# RoverWing-V1_0.net
KiCad netlist of a schematic drawn in EAGLE
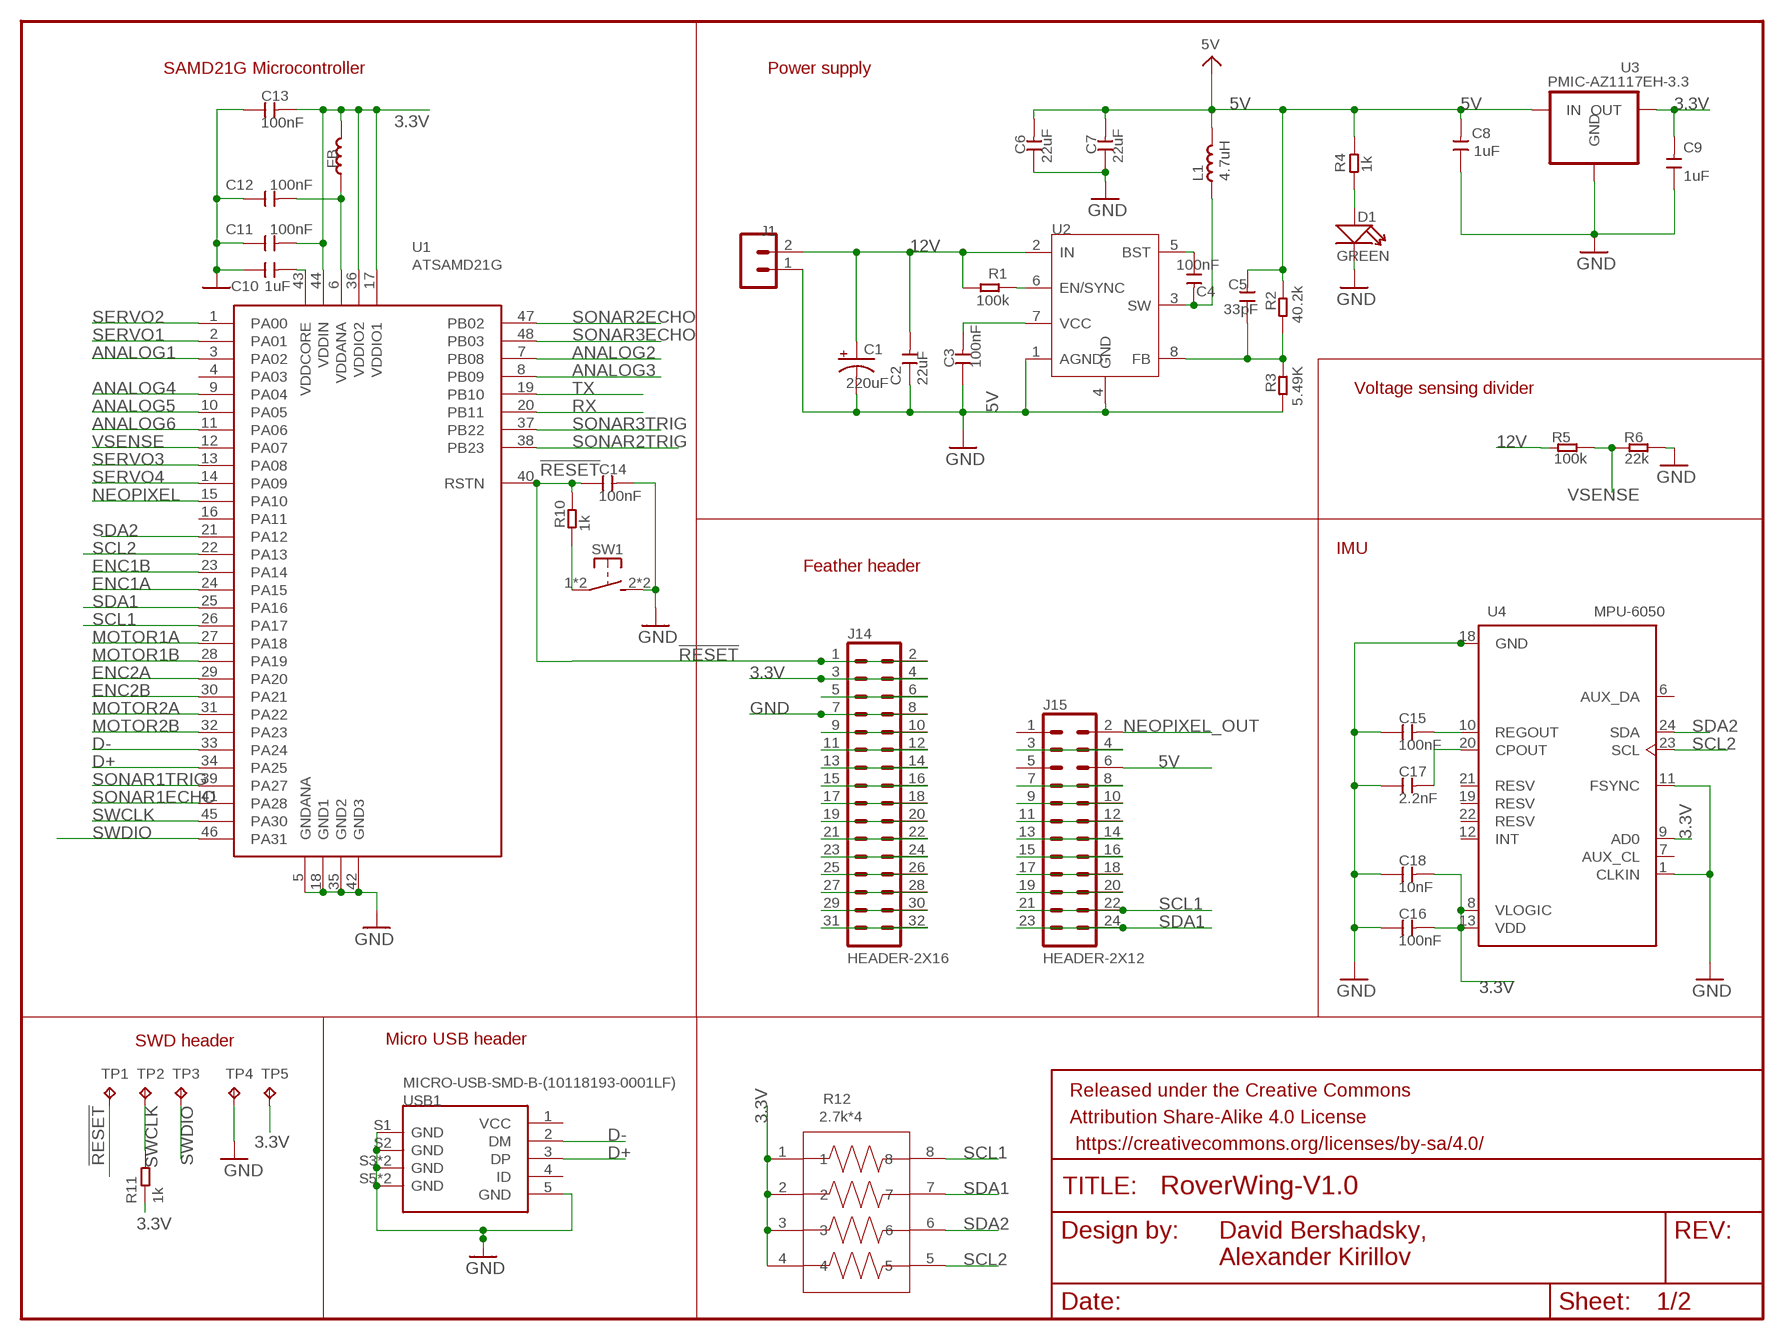
[diagram p0: schematic, sheet 1]
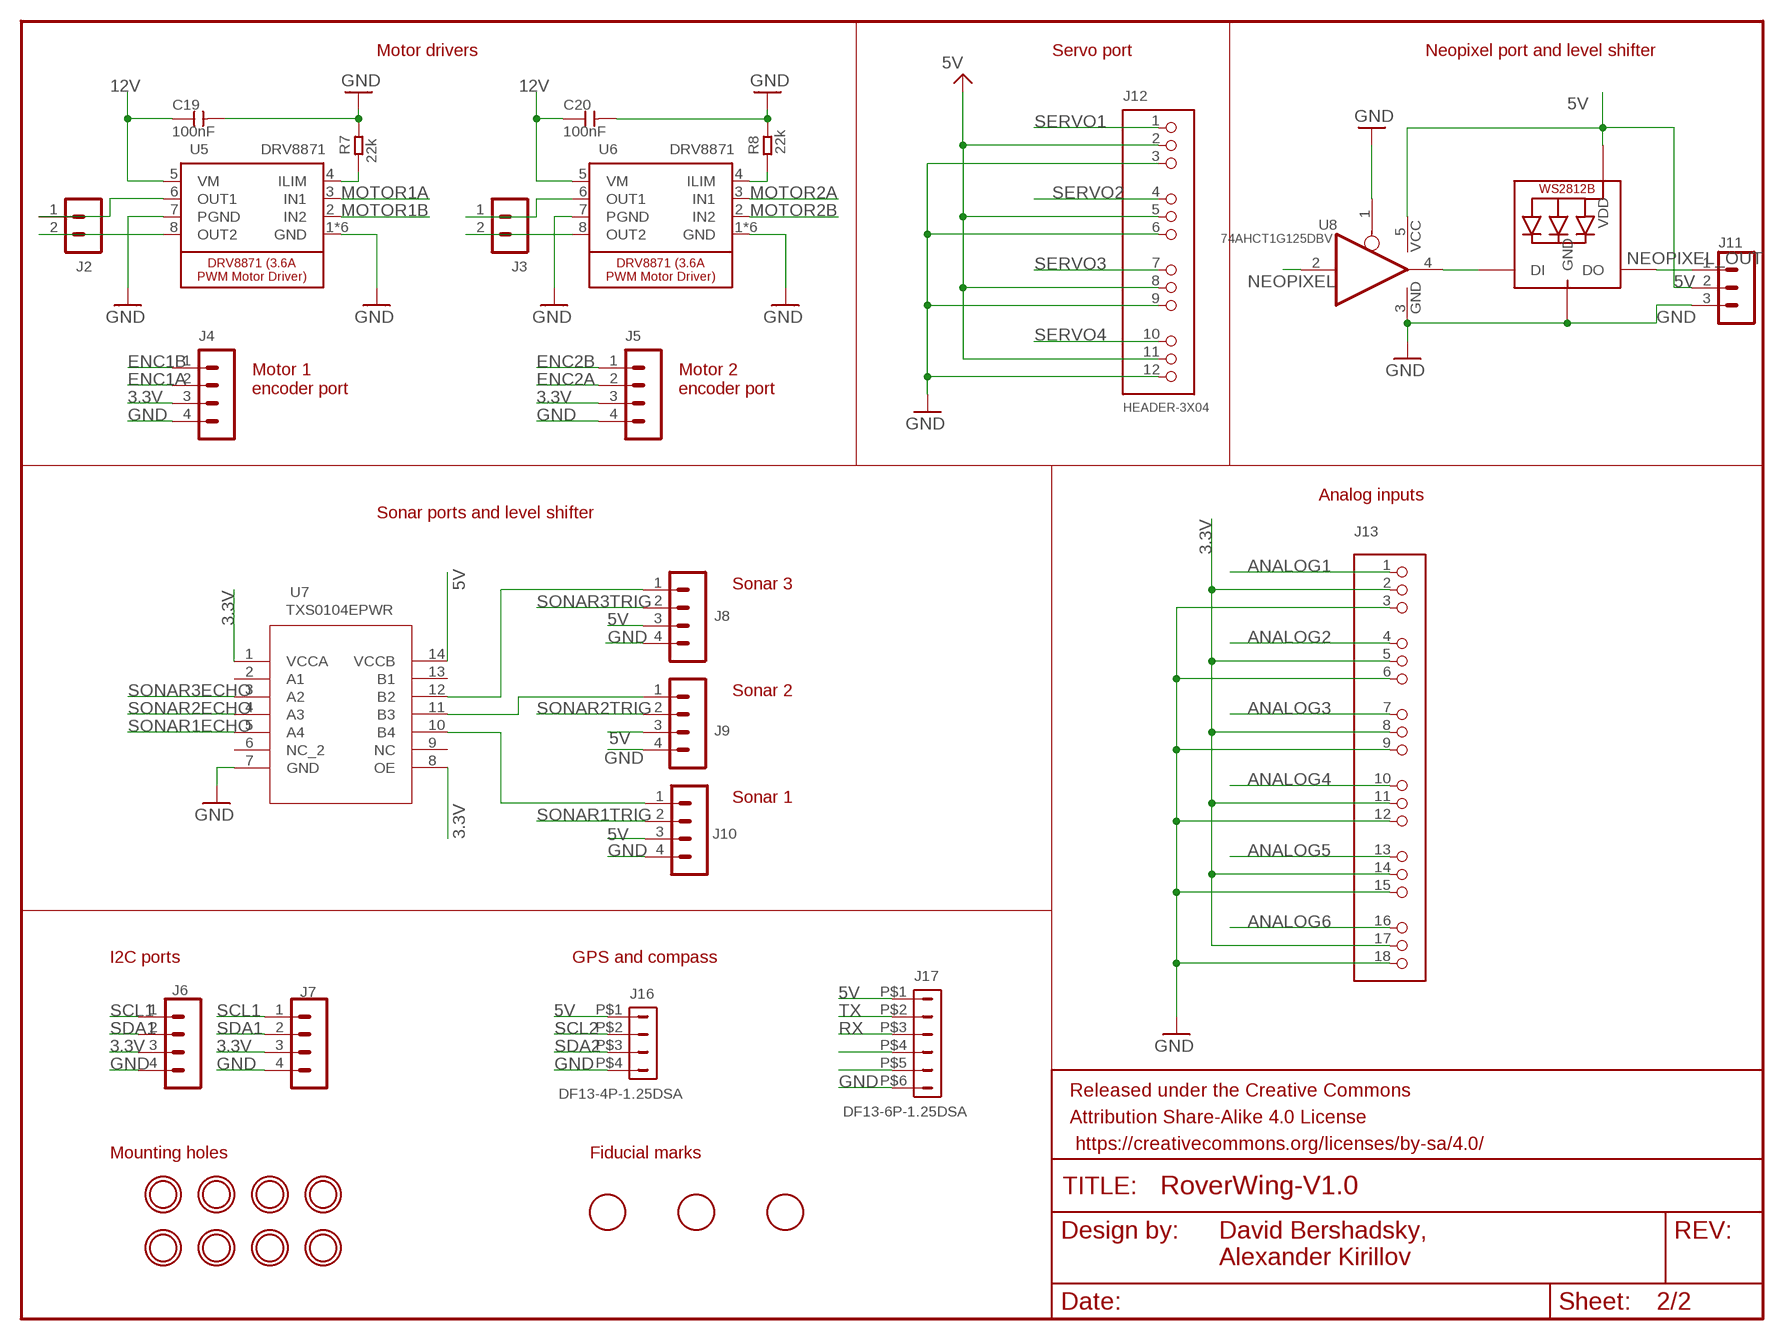
[diagram p1: schematic, sheet 2]

(export (version "E")
  (design (tool "Eeschema 10.0.6"))
  (components
    (comp (ref "C1")
      (value "220uF")
      (footprint "eagle-import:CAP-8X10.5")
      (libsource (lib "eagle-import") (part "CAP-POL-SMD-8X10.5"))
    )
    (comp (ref "C2")
      (value "22uF")
      (footprint "eagle-import:0805")
      (libsource (lib "eagle-import") (part "CAP-CERAMIC-SMD0805"))
    )
    (comp (ref "C3")
      (value "100nF")
      (footprint "eagle-import:0805")
      (libsource (lib "eagle-import") (part "CAP-CERAMIC-SMD0805"))
    )
    (comp (ref "C4")
      (value "100nF")
      (footprint "eagle-import:0805")
      (libsource (lib "eagle-import") (part "CAP-CERAMIC-SMD0805"))
    )
    (comp (ref "C5")
      (value "33pF")
      (footprint "eagle-import:0805")
      (libsource (lib "eagle-import") (part "CAP-CERAMIC-SMD0805"))
    )
    (comp (ref "C6")
      (value "22uF")
      (footprint "eagle-import:0805")
      (libsource (lib "eagle-import") (part "CAP-CERAMIC-SMD0805"))
    )
    (comp (ref "C7")
      (value "22uF")
      (footprint "eagle-import:0805")
      (libsource (lib "eagle-import") (part "CAP-CERAMIC-SMD0805"))
    )
    (comp (ref "C8")
      (value "1uF")
      (footprint "eagle-import:0805")
      (libsource (lib "eagle-import") (part "CAP-CERAMIC-SMD0805"))
    )
    (comp (ref "C9")
      (value "1uF")
      (footprint "eagle-import:0805")
      (libsource (lib "eagle-import") (part "CAP-CERAMIC-SMD0805"))
    )
    (comp (ref "C10")
      (value "1uF")
      (footprint "eagle-import:0805")
      (libsource (lib "eagle-import") (part "CAP-CERAMIC-SMD0805"))
    )
    (comp (ref "C11")
      (value "100nF")
      (footprint "eagle-import:0805")
      (libsource (lib "eagle-import") (part "CAP-CERAMIC-SMD0805"))
    )
    (comp (ref "C12")
      (value "100nF")
      (footprint "eagle-import:0805")
      (libsource (lib "eagle-import") (part "CAP-CERAMIC-SMD0805"))
    )
    (comp (ref "C13")
      (value "100nF")
      (footprint "eagle-import:0805")
      (libsource (lib "eagle-import") (part "CAP-CERAMIC-SMD0805"))
    )
    (comp (ref "C14")
      (value "100nF")
      (footprint "eagle-import:0805")
      (libsource (lib "eagle-import") (part "CAP-CERAMIC-SMD0805"))
    )
    (comp (ref "C15")
      (value "100nF")
      (footprint "eagle-import:0805")
      (libsource (lib "eagle-import") (part "CAP-CERAMIC-SMD0805"))
    )
    (comp (ref "C16")
      (value "100nF")
      (footprint "eagle-import:0805")
      (libsource (lib "eagle-import") (part "CAP-CERAMIC-SMD0805"))
    )
    (comp (ref "C17")
      (value "2.2nF")
      (footprint "eagle-import:0805")
      (libsource (lib "eagle-import") (part "CAP-CERAMIC-SMD0805"))
    )
    (comp (ref "C18")
      (value "10nF")
      (footprint "eagle-import:0805")
      (libsource (lib "eagle-import") (part "CAP-CERAMIC-SMD0805"))
    )
    (comp (ref "D1")
      (value "GREEN")
      (footprint "eagle-import:LED-0805")
      (libsource (lib "eagle-import") (part "SMD-LED-0805"))
    )
    (comp (ref "FB")
      (value "330R-1500MA")
      (footprint "eagle-import:0805")
      (fields (field (name "PARTNO") "BLM21PG331SN1D"))
      (libsource (lib "eagle-import") (part "SMD-FERRITE-BEAD-330R-1500MA(0805)"))
    )
    (comp (ref "FRAME2")
      (value "FRAME-LETTERNO_PACKAGE")
      (footprint "eagle-import:DUMMY")
      (libsource (lib "eagle-import") (part "FRAME-LETTERNO_PACKAGE"))
    )
    (comp (ref "J1")
      (value "HEADER-VH")
      (footprint "eagle-import:B2P-VH")
      (fields (field (name "PARTNO") "B2P-VH(LF)(SN)  "))
      (libsource (lib "eagle-import") (part "HEADER-VH"))
    )
    (comp (ref "J14")
      (value "HEADER-2X16")
      (footprint "eagle-import:2X16")
      (libsource (lib "eagle-import") (part "HEADER-2X16"))
    )
    (comp (ref "J15")
      (value "HEADER-2X12")
      (footprint "eagle-import:2X12")
      (libsource (lib "eagle-import") (part "HEADER-2X12"))
    )
    (comp (ref "L1")
      (value "4.7uH")
      (footprint "eagle-import:IND_TDK_7.1X6.5")
      (fields (field (name "MANUFACTURER") "TDK") (field (name "PARTNO") "SPM6530T-4R7M "))
      (libsource (lib "eagle-import") (part "IND-TDK-SPM6530T"))
    )
    (comp (ref "R1")
      (value "100k")
      (footprint "eagle-import:0805")
      (libsource (lib "eagle-import") (part "RES-SMD-0805"))
    )
    (comp (ref "R2")
      (value "40.2k")
      (footprint "eagle-import:0805")
      (libsource (lib "eagle-import") (part "RES-SMD-0805"))
    )
    (comp (ref "R3")
      (value "5.49K")
      (footprint "eagle-import:0805")
      (libsource (lib "eagle-import") (part "RES-SMD-0805"))
    )
    (comp (ref "R4")
      (value "1k")
      (footprint "eagle-import:0805")
      (libsource (lib "eagle-import") (part "RES-SMD-0805"))
    )
    (comp (ref "R5")
      (value "100k")
      (footprint "eagle-import:0805")
      (libsource (lib "eagle-import") (part "RES-SMD-0805"))
    )
    (comp (ref "R6")
      (value "22k")
      (footprint "eagle-import:0805")
      (libsource (lib "eagle-import") (part "RES-SMD-0805"))
    )
    (comp (ref "R10")
      (value "1k")
      (footprint "eagle-import:0805")
      (libsource (lib "eagle-import") (part "RES-SMD-0805"))
    )
    (comp (ref "R11")
      (value "1k")
      (footprint "eagle-import:0805")
      (libsource (lib "eagle-import") (part "RES-SMD-0805"))
    )
    (comp (ref "R12")
      (value "2.7k*4")
      (footprint "eagle-import:0603_4")
      (fields (field (name "PARTNO") "RTA03-4D272JTP "))
      (libsource (lib "eagle-import") (part "RES_ARRAY-2.7KX40603X4"))
    )
    (comp (ref "SW1")
      (value "SW-TACTILE-4.5X4.5_SMD")
      (footprint "eagle-import:TL3305")
      (fields (field (name "MANUFACTURER") "BRIGHT") (field (name "PARTNO") "TSA453G38-250 "))
      (libsource (lib "eagle-import") (part "SW-TACTILE-4.5X4.5_SMD"))
    )
    (comp (ref "TP1")
      (value "TPTP15R")
      (footprint "eagle-import:TP15R")
      (libsource (lib "eagle-import") (part "TPTP15R"))
    )
    (comp (ref "TP2")
      (value "TPTP15R")
      (footprint "eagle-import:TP15R")
      (libsource (lib "eagle-import") (part "TPTP15R"))
    )
    (comp (ref "TP3")
      (value "TPTP15R")
      (footprint "eagle-import:TP15R")
      (libsource (lib "eagle-import") (part "TPTP15R"))
    )
    (comp (ref "TP4")
      (value "TPTP15R")
      (footprint "eagle-import:TP15R")
      (libsource (lib "eagle-import") (part "TPTP15R"))
    )
    (comp (ref "TP5")
      (value "TPTP15R")
      (footprint "eagle-import:TP15R")
      (libsource (lib "eagle-import") (part "TPTP15R"))
    )
    (comp (ref "U1")
      (value "ATSAMD21G")
      (footprint "eagle-import:TQFP-48-EDITED")
      (fields (field (name "MANUFACTURER") "Microchip Technology") (field (name "PARTNO") "ATSAMD21G18A-AU"))
      (libsource (lib "eagle-import") (part "ATSAMD21G"))
    )
    (comp (ref "U2")
      (value "MP2225")
      (footprint "eagle-import:SOT-23-8")
      (fields (field (name "MANUFACTURER") "Monolithic Power Systems") (field (name "PARTNO") "MP2225GJ"))
      (libsource (lib "eagle-import") (part "PMIC-MP2225"))
    )
    (comp (ref "U3")
      (value "PMIC-AZ1117EH-3.3")
      (footprint "eagle-import:SOT223")
      (fields (field (name "PARTNO") "AZ1117EH-3.3TRG1"))
      (libsource (lib "eagle-import") (part "PMIC-AZ1117EH-3.3"))
    )
    (comp (ref "U4")
      (value "MPU-6050")
      (footprint "eagle-import:QFN50P400X400X95-24N")
      (fields (field (name "MANUFACTURER") "TDK InvenSense"))
      (libsource (lib "eagle-import") (part "MPU-6050"))
    )
    (comp (ref "USB1")
      (value "MICRO-USB-SMD-B-(10118193-0001LF)")
      (footprint "eagle-import:MICRO-USB5+6P-SMD-0.65-B")
      (fields (field (name "MANUFACTURER") "Amphenol ICC") (field (name "PARTNO") "10118193-0001LF"))
      (libsource (lib "eagle-import") (part "MICRO-USB-SMD-B-(10118193-0001LF)"))
    )
    (comp (ref "C19")
      (value "100nF")
      (footprint "eagle-import:0805")
      (libsource (lib "eagle-import") (part "CAP-CERAMIC-SMD0805"))
    )
    (comp (ref "C20")
      (value "100nF")
      (footprint "eagle-import:0805")
      (libsource (lib "eagle-import") (part "CAP-CERAMIC-SMD0805"))
    )
    (comp (ref "FRAME1")
      (value "FRAME-LETTERNO_PACKAGE")
      (footprint "eagle-import:DUMMY")
      (libsource (lib "eagle-import") (part "FRAME-LETTERNO_PACKAGE"))
    )
    (comp (ref "J2")
      (value "HEADER-VH")
      (footprint "eagle-import:B2P-VH")
      (fields (field (name "PARTNO") "B2P-VH(LF)(SN)  "))
      (libsource (lib "eagle-import") (part "HEADER-VH"))
    )
    (comp (ref "J3")
      (value "HEADER-VH")
      (footprint "eagle-import:B2P-VH")
      (fields (field (name "PARTNO") "B2P-VH(LF)(SN)  "))
      (libsource (lib "eagle-import") (part "HEADER-VH"))
    )
    (comp (ref "J4")
      (value "HEADER-PH-4P")
      (footprint "eagle-import:B4B-PH-K")
      (fields (field (name "PARTNO") "B4B-PH-K-S(LF)(SN)"))
      (libsource (lib "eagle-import") (part "HEADER-PH-4P"))
    )
    (comp (ref "J5")
      (value "HEADER-PH-4P")
      (footprint "eagle-import:B4B-PH-K")
      (fields (field (name "PARTNO") "B4B-PH-K-S(LF)(SN)"))
      (libsource (lib "eagle-import") (part "HEADER-PH-4P"))
    )
    (comp (ref "J6")
      (value "HEADER-PH-4P")
      (footprint "eagle-import:B4B-PH-K")
      (fields (field (name "PARTNO") "B4B-PH-K-S(LF)(SN)"))
      (libsource (lib "eagle-import") (part "HEADER-PH-4P"))
    )
    (comp (ref "J7")
      (value "HEADER-PH-4P")
      (footprint "eagle-import:B4B-PH-K")
      (fields (field (name "PARTNO") "B4B-PH-K-S(LF)(SN)"))
      (libsource (lib "eagle-import") (part "HEADER-PH-4P"))
    )
    (comp (ref "J8")
      (value "HEADER-PH-4P")
      (footprint "eagle-import:B4B-PH-K")
      (fields (field (name "PARTNO") "B4B-PH-K-S(LF)(SN)"))
      (libsource (lib "eagle-import") (part "HEADER-PH-4P"))
    )
    (comp (ref "J9")
      (value "HEADER-PH-4P")
      (footprint "eagle-import:B4B-PH-K")
      (fields (field (name "PARTNO") "B4B-PH-K-S(LF)(SN)"))
      (libsource (lib "eagle-import") (part "HEADER-PH-4P"))
    )
    (comp (ref "J10")
      (value "HEADER-PH-4P")
      (footprint "eagle-import:B4B-PH-K")
      (fields (field (name "PARTNO") "B4B-PH-K-S(LF)(SN)"))
      (libsource (lib "eagle-import") (part "HEADER-PH-4P"))
    )
    (comp (ref "J11")
      (value "HEADER-PH-3P")
      (footprint "eagle-import:B3B-PH-K")
      (fields (field (name "PARTNO") "B3B-PH-K-S(LF)(SN)"))
      (libsource (lib "eagle-import") (part "HEADER-PH-3P"))
    )
    (comp (ref "J12")
      (value "HEADER-3X04")
      (footprint "eagle-import:3X04")
      (libsource (lib "eagle-import") (part "HEADER-3X04"))
    )
    (comp (ref "J13")
      (value "HEADER-3X06\"")
      (footprint "eagle-import:3X06")
      (libsource (lib "eagle-import") (part "HEADER-3X06{dblquote}"))
    )
    (comp (ref "J16")
      (value "DF13-4P-1.25DSA")
      (footprint "eagle-import:DF13-4P-1.25DSA")
      (libsource (lib "eagle-import") (part "DF13-4P-1.25DSA"))
    )
    (comp (ref "J17")
      (value "DF13-6P-1.25DSA")
      (footprint "eagle-import:DF13-6P-1.25DSA")
      (libsource (lib "eagle-import") (part "DF13-6P-1.25DSA"))
    )
    (comp (ref "LED1")
      (value "WS2812B3535")
      (footprint "eagle-import:LED3535")
      (fields (field (name "MANUFACTURER") "Worldsemi") (field (name "PARTNO") "WS2812B-3535 "))
      (libsource (lib "eagle-import") (part "WS2812B3535"))
    )
    (comp (ref "R7")
      (value "22k")
      (footprint "eagle-import:0805")
      (libsource (lib "eagle-import") (part "RES-SMD-0805"))
    )
    (comp (ref "R8")
      (value "22k")
      (footprint "eagle-import:0805")
      (libsource (lib "eagle-import") (part "RES-SMD-0805"))
    )
    (comp (ref "U$3")
      (value "MOUNTINGHOLE3.0_NPH")
      (footprint "eagle-import:MOUNTINGHOLE_3.0_NPH")
      (libsource (lib "eagle-import") (part "MOUNTINGHOLE3.0_NPH"))
    )
    (comp (ref "U$4")
      (value "MOUNTINGHOLE3.0_NPH")
      (footprint "eagle-import:MOUNTINGHOLE_3.0_NPH")
      (libsource (lib "eagle-import") (part "MOUNTINGHOLE3.0_NPH"))
    )
    (comp (ref "U$11")
      (value "FIDUCIAL")
      (footprint "eagle-import:FIDUCIAL_1MM")
      (libsource (lib "eagle-import") (part "FIDUCIAL"))
    )
    (comp (ref "U$13")
      (value "FIDUCIAL")
      (footprint "eagle-import:FIDUCIAL_1MM")
      (libsource (lib "eagle-import") (part "FIDUCIAL"))
    )
    (comp (ref "U$14")
      (value "MOUNTINGHOLE3.0_NPH")
      (footprint "eagle-import:MOUNTINGHOLE_3.0_NPH")
      (libsource (lib "eagle-import") (part "MOUNTINGHOLE3.0_NPH"))
    )
    (comp (ref "U$15")
      (value "MOUNTINGHOLE3.0_NPH")
      (footprint "eagle-import:MOUNTINGHOLE_3.0_NPH")
      (libsource (lib "eagle-import") (part "MOUNTINGHOLE3.0_NPH"))
    )
    (comp (ref "U$17")
      (value "FIDUCIAL")
      (footprint "eagle-import:FIDUCIAL_1MM")
      (libsource (lib "eagle-import") (part "FIDUCIAL"))
    )
    (comp (ref "U$24")
      (value "MOUNTINGHOLE3.0_NPH")
      (footprint "eagle-import:MOUNTINGHOLE_3.0_NPH")
      (libsource (lib "eagle-import") (part "MOUNTINGHOLE3.0_NPH"))
    )
    (comp (ref "U$25")
      (value "MOUNTINGHOLE3.0_NPH")
      (footprint "eagle-import:MOUNTINGHOLE_3.0_NPH")
      (libsource (lib "eagle-import") (part "MOUNTINGHOLE3.0_NPH"))
    )
    (comp (ref "U$26")
      (value "MOUNTINGHOLE3.0_NPH")
      (footprint "eagle-import:MOUNTINGHOLE_3.0_NPH")
      (libsource (lib "eagle-import") (part "MOUNTINGHOLE3.0_NPH"))
    )
    (comp (ref "U$27")
      (value "MOUNTINGHOLE3.0_NPH")
      (footprint "eagle-import:MOUNTINGHOLE_3.0_NPH")
      (libsource (lib "eagle-import") (part "MOUNTINGHOLE3.0_NPH"))
    )
    (comp (ref "U5")
      (value "DRV8871")
      (footprint "eagle-import:HSOP8")
      (fields (field (name "MANUFACTURER") "TEXAS INSTRUMENTS") (field (name "PARTNO") "DRV8871DDAR"))
      (libsource (lib "eagle-import") (part "DRV8871"))
    )
    (comp (ref "U6")
      (value "DRV8871")
      (footprint "eagle-import:HSOP8")
      (fields (field (name "MANUFACTURER") "TEXAS INSTRUMENTS") (field (name "PARTNO") "DRV8871DDAR"))
      (libsource (lib "eagle-import") (part "DRV8871"))
    )
    (comp (ref "U7")
      (value "TXS0104EPWR")
      (footprint "eagle-import:PW14")
      (fields (field (name "MANUFACTURER") "Texas Instruments"))
      (libsource (lib "eagle-import") (part "TXS0104EPWR"))
    )
    (comp (ref "U8")
      (value "74AHCT1G125DBV")
      (footprint "eagle-import:SOT23-5")
      (fields (field (name "PARTNO") "SN74AHCT1G125DBVR"))
      (libsource (lib "eagle-import") (part "741G125DBVAHCT"))
    )
  )
  (nets
    (net (code "1") (name "3.3V") (class "Default")
      (node (ref "C11") (pin "2") (pinfunction "2_2") (pintype "passive"))
      (node (ref "C13") (pin "2") (pinfunction "2_2") (pintype "passive"))
      (node (ref "C16") (pin "2") (pinfunction "2_2") (pintype "passive"))
      (node (ref "C18") (pin "2") (pinfunction "2_2") (pintype "passive"))
      (node (ref "C9") (pin "2") (pinfunction "2_2") (pintype "passive"))
      (node (ref "FB") (pin "2") (pinfunction "2_2") (pintype "passive"))
      (node (ref "J13") (pin "11") (pinfunction "11_11") (pintype "passive"))
      (node (ref "J13") (pin "14") (pinfunction "14_14") (pintype "passive"))
      (node (ref "J13") (pin "17") (pinfunction "17_17") (pintype "passive"))
      (node (ref "J13") (pin "2") (pinfunction "2_2") (pintype "passive"))
      (node (ref "J13") (pin "5") (pinfunction "5_5") (pintype "passive"))
      (node (ref "J13") (pin "8") (pinfunction "8_8") (pintype "passive"))
      (node (ref "J14") (pin "3") (pinfunction "3_3") (pintype "passive"))
      (node (ref "J14") (pin "4") (pinfunction "4_4") (pintype "passive"))
      (node (ref "J4") (pin "3") (pinfunction "3_3") (pintype "passive"))
      (node (ref "J5") (pin "3") (pinfunction "3_3") (pintype "passive"))
      (node (ref "J6") (pin "3") (pinfunction "3_3") (pintype "passive"))
      (node (ref "J7") (pin "3") (pinfunction "3_3") (pintype "passive"))
      (node (ref "R11") (pin "1") (pinfunction "1_1") (pintype "passive"))
      (node (ref "R12") (pin "1") (pinfunction "1_1") (pintype "passive"))
      (node (ref "R12") (pin "2") (pinfunction "2_2") (pintype "passive"))
      (node (ref "R12") (pin "3") (pinfunction "3_3") (pintype "passive"))
      (node (ref "R12") (pin "4") (pinfunction "4_4") (pintype "passive"))
      (node (ref "TP5") (pin "TP") (pinfunction "TP_TP") (pintype "input"))
      (node (ref "U1") (pin "17") (pinfunction "VDDIO1_17") (pintype "power_in"))
      (node (ref "U1") (pin "36") (pinfunction "VDDIO2_36") (pintype "power_in"))
      (node (ref "U1") (pin "44") (pinfunction "VDDIN_44") (pintype "power_in"))
      (node (ref "U3") (pin "2") (pinfunction "OUT_2") (pintype "output"))
      (node (ref "U3") (pin "4") (pinfunction "OUT_4") (pintype "output"))
      (node (ref "U4") (pin "13") (pinfunction "VDD_13") (pintype "power_in"))
      (node (ref "U4") (pin "8") (pinfunction "VLOGIC_8") (pintype "power_in"))
      (node (ref "U4") (pin "9") (pinfunction "AD0_9") (pintype "input"))
      (node (ref "U7") (pin "1") (pinfunction "VCCA_1") (pintype "power_in"))
      (node (ref "U7") (pin "8") (pinfunction "OE_8") (pintype "output"))
    )
    (net (code "2") (name "5V") (class "Default")
      (node (ref "C5") (pin "2") (pinfunction "2_2") (pintype "passive"))
      (node (ref "C6") (pin "2") (pinfunction "2_2") (pintype "passive"))
      (node (ref "C7") (pin "2") (pinfunction "2_2") (pintype "passive"))
      (node (ref "C8") (pin "2") (pinfunction "2_2") (pintype "passive"))
      (node (ref "J10") (pin "3") (pinfunction "3_3") (pintype "passive"))
      (node (ref "J11") (pin "2") (pinfunction "2_2") (pintype "passive"))
      (node (ref "J12") (pin "11") (pinfunction "11_11") (pintype "passive"))
      (node (ref "J12") (pin "2") (pinfunction "2_2") (pintype "passive"))
      (node (ref "J12") (pin "5") (pinfunction "5_5") (pintype "passive"))
      (node (ref "J12") (pin "8") (pinfunction "8_8") (pintype "passive"))
      (node (ref "J15") (pin "6") (pinfunction "6_6") (pintype "passive"))
      (node (ref "J16") (pin "P$1") (pinfunction "1_P$1") (pintype "passive"))
      (node (ref "J17") (pin "P$1") (pinfunction "1_P$1") (pintype "passive"))
      (node (ref "J8") (pin "3") (pinfunction "3_3") (pintype "passive"))
      (node (ref "J9") (pin "3") (pinfunction "3_3") (pintype "passive"))
      (node (ref "L1") (pin "2") (pinfunction "2_2") (pintype "passive"))
      (node (ref "LED1") (pin "3") (pinfunction "VDD_3") (pintype "power_in"))
      (node (ref "R2") (pin "1") (pinfunction "1_1") (pintype "passive"))
      (node (ref "R4") (pin "2") (pinfunction "2_2") (pintype "passive"))
      (node (ref "U3") (pin "3") (pinfunction "IN_3") (pintype "input"))
      (node (ref "U7") (pin "14") (pinfunction "VCCB_14") (pintype "power_in"))
      (node (ref "U8") (pin "5") (pinfunction "VCC_5") (pintype "power_in"))
    )
    (net (code "3") (name "12V") (class "Default")
      (node (ref "C1") (pin "+") (pinfunction "+_+") (pintype "passive"))
      (node (ref "C19") (pin "1") (pinfunction "1_1") (pintype "passive"))
      (node (ref "C2") (pin "2") (pinfunction "2_2") (pintype "passive"))
      (node (ref "C20") (pin "1") (pinfunction "1_1") (pintype "passive"))
      (node (ref "J1") (pin "2") (pinfunction "2_2") (pintype "passive"))
      (node (ref "R1") (pin "2") (pinfunction "2_2") (pintype "passive"))
      (node (ref "R5") (pin "2") (pinfunction "2_2") (pintype "passive"))
      (node (ref "U2") (pin "2") (pinfunction "IN_2") (pintype "bidirectional"))
      (node (ref "U5") (pin "5") (pinfunction "VM_5") (pintype "power_in"))
      (node (ref "U6") (pin "5") (pinfunction "VM_5") (pintype "power_in"))
    )
    (net (code "4") (name "ANALOG1") (class "Default")
      (node (ref "J13") (pin "1") (pinfunction "1_1") (pintype "passive"))
      (node (ref "U1") (pin "3") (pinfunction "PA02_3") (pintype "bidirectional"))
    )
    (net (code "5") (name "ANALOG2") (class "Default")
      (node (ref "J13") (pin "4") (pinfunction "4_4") (pintype "passive"))
      (node (ref "U1") (pin "7") (pinfunction "PB08_7") (pintype "bidirectional"))
    )
    (net (code "6") (name "ANALOG3") (class "Default")
      (node (ref "J13") (pin "7") (pinfunction "7_7") (pintype "passive"))
      (node (ref "U1") (pin "8") (pinfunction "PB09_8") (pintype "bidirectional"))
    )
    (net (code "7") (name "ANALOG4") (class "Default")
      (node (ref "J13") (pin "10") (pinfunction "10_10") (pintype "passive"))
      (node (ref "U1") (pin "9") (pinfunction "PA04_9") (pintype "bidirectional"))
    )
    (net (code "8") (name "ANALOG5") (class "Default")
      (node (ref "J13") (pin "13") (pinfunction "13_13") (pintype "passive"))
      (node (ref "U1") (pin "10") (pinfunction "PA05_10") (pintype "bidirectional"))
    )
    (net (code "9") (name "ANALOG6") (class "Default")
      (node (ref "J13") (pin "16") (pinfunction "16_16") (pintype "passive"))
      (node (ref "U1") (pin "11") (pinfunction "PA06_11") (pintype "bidirectional"))
    )
    (net (code "10") (name "D+") (class "Default")
      (node (ref "U1") (pin "34") (pinfunction "PA25_34") (pintype "bidirectional"))
      (node (ref "USB1") (pin "3") (pinfunction "DP_3") (pintype "bidirectional"))
    )
    (net (code "11") (name "D-") (class "Default")
      (node (ref "U1") (pin "33") (pinfunction "PA24_33") (pintype "bidirectional"))
      (node (ref "USB1") (pin "2") (pinfunction "DM_2") (pintype "bidirectional"))
    )
    (net (code "12") (name "ENC1A") (class "Default")
      (node (ref "J4") (pin "2") (pinfunction "2_2") (pintype "passive"))
      (node (ref "U1") (pin "24") (pinfunction "PA15_24") (pintype "bidirectional"))
    )
    (net (code "13") (name "ENC1B") (class "Default")
      (node (ref "J4") (pin "1") (pinfunction "1_1") (pintype "passive"))
      (node (ref "U1") (pin "23") (pinfunction "PA14_23") (pintype "bidirectional"))
    )
    (net (code "14") (name "ENC2A") (class "Default")
      (node (ref "J5") (pin "2") (pinfunction "2_2") (pintype "passive"))
      (node (ref "U1") (pin "29") (pinfunction "PA20_29") (pintype "bidirectional"))
    )
    (net (code "15") (name "ENC2B") (class "Default")
      (node (ref "J5") (pin "1") (pinfunction "1_1") (pintype "passive"))
      (node (ref "U1") (pin "30") (pinfunction "PA21_30") (pintype "bidirectional"))
    )
    (net (code "16") (name "GND") (class "Default")
      (node (ref "C1") (pin "-") (pinfunction "-_-") (pintype "passive"))
      (node (ref "C10") (pin "1") (pinfunction "1_1") (pintype "passive"))
      (node (ref "C11") (pin "1") (pinfunction "1_1") (pintype "passive"))
      (node (ref "C12") (pin "1") (pinfunction "1_1") (pintype "passive"))
      (node (ref "C13") (pin "1") (pinfunction "1_1") (pintype "passive"))
      (node (ref "C14") (pin "2") (pinfunction "2_2") (pintype "passive"))
      (node (ref "C15") (pin "1") (pinfunction "1_1") (pintype "passive"))
      (node (ref "C16") (pin "1") (pinfunction "1_1") (pintype "passive"))
      (node (ref "C17") (pin "1") (pinfunction "1_1") (pintype "passive"))
      (node (ref "C18") (pin "1") (pinfunction "1_1") (pintype "passive"))
      (node (ref "C19") (pin "2") (pinfunction "2_2") (pintype "passive"))
      (node (ref "C2") (pin "1") (pinfunction "1_1") (pintype "passive"))
      (node (ref "C20") (pin "2") (pinfunction "2_2") (pintype "passive"))
      (node (ref "C3") (pin "1") (pinfunction "1_1") (pintype "passive"))
      (node (ref "C6") (pin "1") (pinfunction "1_1") (pintype "passive"))
      (node (ref "C7") (pin "1") (pinfunction "1_1") (pintype "passive"))
      (node (ref "C8") (pin "1") (pinfunction "1_1") (pintype "passive"))
      (node (ref "C9") (pin "1") (pinfunction "1_1") (pintype "passive"))
      (node (ref "D1") (pin "-") (pinfunction "-_-") (pintype "passive"))
      (node (ref "J1") (pin "1") (pinfunction "1_1") (pintype "passive"))
      (node (ref "J10") (pin "4") (pinfunction "4_4") (pintype "passive"))
      (node (ref "J11") (pin "3") (pinfunction "3_3") (pintype "passive"))
      (node (ref "J12") (pin "12") (pinfunction "12_12") (pintype "passive"))
      (node (ref "J12") (pin "3") (pinfunction "3_3") (pintype "passive"))
      (node (ref "J12") (pin "6") (pinfunction "6_6") (pintype "passive"))
      (node (ref "J12") (pin "9") (pinfunction "9_9") (pintype "passive"))
      (node (ref "J13") (pin "12") (pinfunction "12_12") (pintype "passive"))
      (node (ref "J13") (pin "15") (pinfunction "15_15") (pintype "passive"))
      (node (ref "J13") (pin "18") (pinfunction "18_18") (pintype "passive"))
      (node (ref "J13") (pin "3") (pinfunction "3_3") (pintype "passive"))
      (node (ref "J13") (pin "6") (pinfunction "6_6") (pintype "passive"))
      (node (ref "J13") (pin "9") (pinfunction "9_9") (pintype "passive"))
      (node (ref "J14") (pin "7") (pinfunction "7_7") (pintype "passive"))
      (node (ref "J14") (pin "8") (pinfunction "8_8") (pintype "passive"))
      (node (ref "J16") (pin "P$4") (pinfunction "4_P$4") (pintype "passive"))
      (node (ref "J17") (pin "P$6") (pinfunction "6_P$6") (pintype "passive"))
      (node (ref "J4") (pin "4") (pinfunction "4_4") (pintype "passive"))
      (node (ref "J5") (pin "4") (pinfunction "4_4") (pintype "passive"))
      (node (ref "J6") (pin "4") (pinfunction "4_4") (pintype "passive"))
      (node (ref "J7") (pin "4") (pinfunction "4_4") (pintype "passive"))
      (node (ref "J8") (pin "4") (pinfunction "4_4") (pintype "passive"))
      (node (ref "J9") (pin "4") (pinfunction "4_4") (pintype "passive"))
      (node (ref "LED1") (pin "1") (pinfunction "GND_1") (pintype "power_in"))
      (node (ref "R3") (pin "2") (pinfunction "2_2") (pintype "passive"))
      (node (ref "R6") (pin "2") (pinfunction "2_2") (pintype "passive"))
      (node (ref "R7") (pin "2") (pinfunction "2_2") (pintype "passive"))
      (node (ref "R8") (pin "2") (pinfunction "2_2") (pintype "passive"))
      (node (ref "SW1") (pin "2") (pinfunction "S1_2") (pintype "passive"))
      (node (ref "SW1") (pin "3") (pinfunction "S1_3") (pintype "passive"))
      (node (ref "TP4") (pin "TP") (pinfunction "TP_TP") (pintype "input"))
      (node (ref "U1") (pin "18") (pinfunction "GND1_18") (pintype "power_in"))
      (node (ref "U1") (pin "35") (pinfunction "GND2_35") (pintype "power_in"))
      (node (ref "U1") (pin "42") (pinfunction "GND3_42") (pintype "power_in"))
      (node (ref "U1") (pin "5") (pinfunction "GNDANA_5") (pintype "power_in"))
      (node (ref "U2") (pin "1") (pinfunction "AGND_1") (pintype "bidirectional"))
      (node (ref "U2") (pin "4") (pinfunction "GND_4") (pintype "bidirectional"))
      (node (ref "U3") (pin "1") (pinfunction "GND_1") (pintype "power_in"))
      (node (ref "U4") (pin "1") (pinfunction "CLKIN_1") (pintype "input"))
      (node (ref "U4") (pin "11") (pinfunction "FSYNC_11") (pintype "input"))
      (node (ref "U4") (pin "18") (pinfunction "GND_18") (pintype "power_in"))
      (node (ref "U5") (pin "1") (pinfunction "GND_1") (pintype "power_in"))
      (node (ref "U5") (pin "7") (pinfunction "PGND_7") (pintype "power_in"))
      (node (ref "U5") (pin "GND") (pinfunction "GND_GND") (pintype "power_in"))
      (node (ref "U5") (pin "P$1") (pinfunction "GND_P$1") (pintype "power_in"))
      (node (ref "U5") (pin "P$2") (pinfunction "GND_P$2") (pintype "power_in"))
      (node (ref "U5") (pin "P$3") (pinfunction "GND_P$3") (pintype "power_in"))
      (node (ref "U5") (pin "P$4") (pinfunction "GND_P$4") (pintype "power_in"))
      (node (ref "U6") (pin "1") (pinfunction "GND_1") (pintype "power_in"))
      (node (ref "U6") (pin "7") (pinfunction "PGND_7") (pintype "power_in"))
      (node (ref "U6") (pin "GND") (pinfunction "GND_GND") (pintype "power_in"))
      (node (ref "U6") (pin "P$1") (pinfunction "GND_P$1") (pintype "power_in"))
      (node (ref "U6") (pin "P$2") (pinfunction "GND_P$2") (pintype "power_in"))
      (node (ref "U6") (pin "P$3") (pinfunction "GND_P$3") (pintype "power_in"))
      (node (ref "U6") (pin "P$4") (pinfunction "GND_P$4") (pintype "power_in"))
      (node (ref "U7") (pin "7") (pinfunction "GND_7") (pintype "power_in"))
      (node (ref "U8") (pin "1") (pinfunction "OE_1") (pintype "input"))
      (node (ref "U8") (pin "3") (pinfunction "GND_3") (pintype "power_in"))
      (node (ref "USB1") (pin "5") (pinfunction "GND_5") (pintype "bidirectional"))
      (node (ref "USB1") (pin "S1") (pinfunction "GND_S1") (pintype "bidirectional"))
      (node (ref "USB1") (pin "S2") (pinfunction "GND_S2") (pintype "bidirectional"))
      (node (ref "USB1") (pin "S3") (pinfunction "GND_S3") (pintype "bidirectional"))
      (node (ref "USB1") (pin "S4") (pinfunction "GND_S4") (pintype "bidirectional"))
      (node (ref "USB1") (pin "S5") (pinfunction "GND_S5") (pintype "bidirectional"))
      (node (ref "USB1") (pin "S6") (pinfunction "GND_S6") (pintype "bidirectional"))
    )
    (net (code "17") (name "MOTOR1A") (class "Default")
      (node (ref "U1") (pin "27") (pinfunction "PA18_27") (pintype "bidirectional"))
      (node (ref "U5") (pin "3") (pinfunction "IN1_3") (pintype "input"))
    )
    (net (code "18") (name "MOTOR1B") (class "Default")
      (node (ref "U1") (pin "28") (pinfunction "PA19_28") (pintype "bidirectional"))
      (node (ref "U5") (pin "2") (pinfunction "IN2_2") (pintype "input"))
    )
    (net (code "19") (name "MOTOR2A") (class "Default")
      (node (ref "U1") (pin "31") (pinfunction "PA22_31") (pintype "bidirectional"))
      (node (ref "U6") (pin "3") (pinfunction "IN1_3") (pintype "input"))
    )
    (net (code "20") (name "MOTOR2B") (class "Default")
      (node (ref "U1") (pin "32") (pinfunction "PA23_32") (pintype "bidirectional"))
      (node (ref "U6") (pin "2") (pinfunction "IN2_2") (pintype "input"))
    )
    (net (code "21") (name "NEOPIXEL") (class "Default")
      (node (ref "U1") (pin "15") (pinfunction "PA10_15") (pintype "bidirectional"))
      (node (ref "U8") (pin "2") (pinfunction "I_2") (pintype "input"))
    )
    (net (code "22") (name "NEOPIXEL_OUT") (class "Default")
      (node (ref "J11") (pin "1") (pinfunction "1_1") (pintype "passive"))
      (node (ref "J15") (pin "2") (pinfunction "2_2") (pintype "passive"))
      (node (ref "LED1") (pin "4") (pinfunction "DO_4") (pintype "output"))
    )
    (net (code "23") (name "Net-(D1-Pad+)") (class "Default")
      (node (ref "D1") (pin "+") (pinfunction "+_+") (pintype "passive"))
      (node (ref "R4") (pin "1") (pinfunction "1_1") (pintype "passive"))
    )
    (net (code "24") (name "Net-(J14-Pad5)") (class "Default")
      (node (ref "J14") (pin "5") (pinfunction "5_5") (pintype "passive"))
      (node (ref "J14") (pin "6") (pinfunction "6_6") (pintype "passive"))
    )
    (net (code "25") (name "Net-(J14-Pad10)") (class "Default")
      (node (ref "J14") (pin "10") (pinfunction "10_10") (pintype "passive"))
      (node (ref "J14") (pin "9") (pinfunction "9_9") (pintype "passive"))
    )
    (net (code "26") (name "Net-(J14-Pad11)") (class "Default")
      (node (ref "J14") (pin "11") (pinfunction "11_11") (pintype "passive"))
      (node (ref "J14") (pin "12") (pinfunction "12_12") (pintype "passive"))
    )
    (net (code "27") (name "Net-(J14-Pad13)") (class "Default")
      (node (ref "J14") (pin "13") (pinfunction "13_13") (pintype "passive"))
      (node (ref "J14") (pin "14") (pinfunction "14_14") (pintype "passive"))
    )
    (net (code "28") (name "Net-(J14-Pad15)") (class "Default")
      (node (ref "J14") (pin "15") (pinfunction "15_15") (pintype "passive"))
      (node (ref "J14") (pin "16") (pinfunction "16_16") (pintype "passive"))
    )
    (net (code "29") (name "Net-(J14-Pad17)") (class "Default")
      (node (ref "J14") (pin "17") (pinfunction "17_17") (pintype "passive"))
      (node (ref "J14") (pin "18") (pinfunction "18_18") (pintype "passive"))
    )
    (net (code "30") (name "Net-(J14-Pad19)") (class "Default")
      (node (ref "J14") (pin "19") (pinfunction "19_19") (pintype "passive"))
      (node (ref "J14") (pin "20") (pinfunction "20_20") (pintype "passive"))
    )
    (net (code "31") (name "Net-(J14-Pad21)") (class "Default")
      (node (ref "J14") (pin "21") (pinfunction "21_21") (pintype "passive"))
      (node (ref "J14") (pin "22") (pinfunction "22_22") (pintype "passive"))
    )
    (net (code "32") (name "Net-(J14-Pad23)") (class "Default")
      (node (ref "J14") (pin "23") (pinfunction "23_23") (pintype "passive"))
      (node (ref "J14") (pin "24") (pinfunction "24_24") (pintype "passive"))
    )
    (net (code "33") (name "Net-(J14-Pad25)") (class "Default")
      (node (ref "J14") (pin "25") (pinfunction "25_25") (pintype "passive"))
      (node (ref "J14") (pin "26") (pinfunction "26_26") (pintype "passive"))
    )
    (net (code "34") (name "Net-(J14-Pad27)") (class "Default")
      (node (ref "J14") (pin "27") (pinfunction "27_27") (pintype "passive"))
      (node (ref "J14") (pin "28") (pinfunction "28_28") (pintype "passive"))
    )
    (net (code "35") (name "Net-(J14-Pad29)") (class "Default")
      (node (ref "J14") (pin "29") (pinfunction "29_29") (pintype "passive"))
      (node (ref "J14") (pin "30") (pinfunction "30_30") (pintype "passive"))
    )
    (net (code "36") (name "Net-(J14-Pad31)") (class "Default")
      (node (ref "J14") (pin "31") (pinfunction "31_31") (pintype "passive"))
      (node (ref "J14") (pin "32") (pinfunction "32_32") (pintype "passive"))
    )
    (net (code "37") (name "Net-(J15-Pad3)") (class "Default")
      (node (ref "J15") (pin "3") (pinfunction "3_3") (pintype "passive"))
      (node (ref "J15") (pin "4") (pinfunction "4_4") (pintype "passive"))
    )
    (net (code "38") (name "Net-(J15-Pad7)") (class "Default")
      (node (ref "J15") (pin "7") (pinfunction "7_7") (pintype "passive"))
      (node (ref "J15") (pin "8") (pinfunction "8_8") (pintype "passive"))
    )
    (net (code "39") (name "Net-(J15-Pad10)") (class "Default")
      (node (ref "J15") (pin "10") (pinfunction "10_10") (pintype "passive"))
      (node (ref "J15") (pin "9") (pinfunction "9_9") (pintype "passive"))
    )
    (net (code "40") (name "Net-(J15-Pad11)") (class "Default")
      (node (ref "J15") (pin "11") (pinfunction "11_11") (pintype "passive"))
      (node (ref "J15") (pin "12") (pinfunction "12_12") (pintype "passive"))
    )
    (net (code "41") (name "Net-(J15-Pad13)") (class "Default")
      (node (ref "J15") (pin "13") (pinfunction "13_13") (pintype "passive"))
      (node (ref "J15") (pin "14") (pinfunction "14_14") (pintype "passive"))
    )
    (net (code "42") (name "Net-(J15-Pad15)") (class "Default")
      (node (ref "J15") (pin "15") (pinfunction "15_15") (pintype "passive"))
      (node (ref "J15") (pin "16") (pinfunction "16_16") (pintype "passive"))
    )
    (net (code "43") (name "Net-(J15-Pad17)") (class "Default")
      (node (ref "J15") (pin "17") (pinfunction "17_17") (pintype "passive"))
      (node (ref "J15") (pin "18") (pinfunction "18_18") (pintype "passive"))
    )
    (net (code "44") (name "Net-(J15-Pad19)") (class "Default")
      (node (ref "J15") (pin "19") (pinfunction "19_19") (pintype "passive"))
      (node (ref "J15") (pin "20") (pinfunction "20_20") (pintype "passive"))
    )
    (net (code "45") (name "Net-(LED1-DI)") (class "Default")
      (node (ref "LED1") (pin "2") (pinfunction "DI_2") (pintype "input"))
      (node (ref "U8") (pin "4") (pinfunction "O_4") (pintype "tri_state"))
    )
    (net (code "46") (name "Net-(R10-Pad1)") (class "Default")
      (node (ref "R10") (pin "1") (pinfunction "1_1") (pintype "passive"))
      (node (ref "SW1") (pin "1") (pinfunction "P1_1") (pintype "passive"))
      (node (ref "SW1") (pin "4") (pinfunction "P1_4") (pintype "passive"))
    )
    (net (code "47") (name "Net-(U1-VDDANA)") (class "Default")
      (node (ref "C12") (pin "2") (pinfunction "2_2") (pintype "passive"))
      (node (ref "FB") (pin "1") (pinfunction "1_1") (pintype "passive"))
      (node (ref "U1") (pin "6") (pinfunction "VDDANA_6") (pintype "power_in"))
    )
    (net (code "48") (name "Net-(U1-VDDCORE)") (class "Default")
      (node (ref "C10") (pin "2") (pinfunction "2_2") (pintype "passive"))
      (node (ref "U1") (pin "43") (pinfunction "VDDCORE_43") (pintype "power_in"))
    )
    (net (code "49") (name "Net-(U2-BST)") (class "Default")
      (node (ref "C4") (pin "1") (pinfunction "1_1") (pintype "passive"))
      (node (ref "U2") (pin "5") (pinfunction "BST_5") (pintype "bidirectional"))
    )
    (net (code "50") (name "Net-(U2-EN{slash}SYNC)") (class "Default")
      (node (ref "R1") (pin "1") (pinfunction "1_1") (pintype "passive"))
      (node (ref "U2") (pin "6") (pinfunction "EN/SYNC_6") (pintype "bidirectional"))
    )
    (net (code "51") (name "Net-(U2-FB)") (class "Default")
      (node (ref "C5") (pin "1") (pinfunction "1_1") (pintype "passive"))
      (node (ref "R2") (pin "2") (pinfunction "2_2") (pintype "passive"))
      (node (ref "R3") (pin "1") (pinfunction "1_1") (pintype "passive"))
      (node (ref "U2") (pin "8") (pinfunction "FB_8") (pintype "bidirectional"))
    )
    (net (code "52") (name "Net-(U2-SW)") (class "Default")
      (node (ref "C4") (pin "2") (pinfunction "2_2") (pintype "passive"))
      (node (ref "L1") (pin "1") (pinfunction "1_1") (pintype "passive"))
      (node (ref "U2") (pin "3") (pinfunction "SW_3") (pintype "bidirectional"))
    )
    (net (code "53") (name "Net-(U2-VCC)") (class "Default")
      (node (ref "C3") (pin "2") (pinfunction "2_2") (pintype "passive"))
      (node (ref "U2") (pin "7") (pinfunction "VCC_7") (pintype "bidirectional"))
    )
    (net (code "54") (name "Net-(U4-CPOUT)") (class "Default")
      (node (ref "C17") (pin "2") (pinfunction "2_2") (pintype "passive"))
      (node (ref "U4") (pin "20") (pinfunction "CPOUT_20") (pintype "passive"))
    )
    (net (code "55") (name "Net-(U4-REGOUT)") (class "Default")
      (node (ref "C15") (pin "2") (pinfunction "2_2") (pintype "passive"))
      (node (ref "U4") (pin "10") (pinfunction "REGOUT_10") (pintype "passive"))
    )
    (net (code "56") (name "Net-(U5-ILIM)") (class "Default")
      (node (ref "R7") (pin "1") (pinfunction "1_1") (pintype "passive"))
      (node (ref "U5") (pin "4") (pinfunction "ILIM_4") (pintype "input"))
    )
    (net (code "57") (name "Net-(U5-OUT1)") (class "Default")
      (node (ref "J2") (pin "1") (pinfunction "1_1") (pintype "passive"))
      (node (ref "U5") (pin "6") (pinfunction "OUT1_6") (pintype "output"))
    )
    (net (code "58") (name "Net-(U5-OUT2)") (class "Default")
      (node (ref "J2") (pin "2") (pinfunction "2_2") (pintype "passive"))
      (node (ref "U5") (pin "8") (pinfunction "OUT2_8") (pintype "output"))
    )
    (net (code "59") (name "Net-(U6-ILIM)") (class "Default")
      (node (ref "R8") (pin "1") (pinfunction "1_1") (pintype "passive"))
      (node (ref "U6") (pin "4") (pinfunction "ILIM_4") (pintype "input"))
    )
    (net (code "60") (name "Net-(U6-OUT1)") (class "Default")
      (node (ref "J3") (pin "1") (pinfunction "1_1") (pintype "passive"))
      (node (ref "U6") (pin "6") (pinfunction "OUT1_6") (pintype "output"))
    )
    (net (code "61") (name "Net-(U6-OUT2)") (class "Default")
      (node (ref "J3") (pin "2") (pinfunction "2_2") (pintype "passive"))
      (node (ref "U6") (pin "8") (pinfunction "OUT2_8") (pintype "output"))
    )
    (net (code "62") (name "Net-(U7-B2)") (class "Default")
      (node (ref "J8") (pin "1") (pinfunction "1_1") (pintype "passive"))
      (node (ref "U7") (pin "12") (pinfunction "B2_12") (pintype "bidirectional"))
    )
    (net (code "63") (name "Net-(U7-B3)") (class "Default")
      (node (ref "J9") (pin "1") (pinfunction "1_1") (pintype "passive"))
      (node (ref "U7") (pin "11") (pinfunction "B3_11") (pintype "bidirectional"))
    )
    (net (code "64") (name "Net-(U7-B4)") (class "Default")
      (node (ref "J10") (pin "1") (pinfunction "1_1") (pintype "passive"))
      (node (ref "U7") (pin "10") (pinfunction "B4_10") (pintype "bidirectional"))
    )
    (net (code "65") (name "RX") (class "Default")
      (node (ref "J17") (pin "P$3") (pinfunction "3_P$3") (pintype "passive"))
      (node (ref "U1") (pin "20") (pinfunction "PB11_20") (pintype "bidirectional"))
    )
    (net (code "66") (name "SCL1") (class "Default")
      (node (ref "J15") (pin "21") (pinfunction "21_21") (pintype "passive"))
      (node (ref "J15") (pin "22") (pinfunction "22_22") (pintype "passive"))
      (node (ref "J6") (pin "1") (pinfunction "1_1") (pintype "passive"))
      (node (ref "J7") (pin "1") (pinfunction "1_1") (pintype "passive"))
      (node (ref "R12") (pin "8") (pinfunction "8_8") (pintype "passive"))
      (node (ref "U1") (pin "26") (pinfunction "PA17_26") (pintype "bidirectional"))
    )
    (net (code "67") (name "SCL2") (class "Default")
      (node (ref "J16") (pin "P$2") (pinfunction "2_P$2") (pintype "passive"))
      (node (ref "R12") (pin "5") (pinfunction "5_5") (pintype "passive"))
      (node (ref "U1") (pin "22") (pinfunction "PA13_22") (pintype "bidirectional"))
      (node (ref "U4") (pin "23") (pinfunction "SCL_23") (pintype "input"))
    )
    (net (code "68") (name "SDA1") (class "Default")
      (node (ref "J15") (pin "23") (pinfunction "23_23") (pintype "passive"))
      (node (ref "J15") (pin "24") (pinfunction "24_24") (pintype "passive"))
      (node (ref "J6") (pin "2") (pinfunction "2_2") (pintype "passive"))
      (node (ref "J7") (pin "2") (pinfunction "2_2") (pintype "passive"))
      (node (ref "R12") (pin "7") (pinfunction "7_7") (pintype "passive"))
      (node (ref "U1") (pin "25") (pinfunction "PA16_25") (pintype "bidirectional"))
    )
    (net (code "69") (name "SDA2") (class "Default")
      (node (ref "J16") (pin "P$3") (pinfunction "3_P$3") (pintype "passive"))
      (node (ref "R12") (pin "6") (pinfunction "6_6") (pintype "passive"))
      (node (ref "U1") (pin "21") (pinfunction "PA12_21") (pintype "bidirectional"))
      (node (ref "U4") (pin "24") (pinfunction "SDA_24") (pintype "bidirectional"))
    )
    (net (code "70") (name "SERVO1") (class "Default")
      (node (ref "J12") (pin "1") (pinfunction "1_1") (pintype "passive"))
      (node (ref "U1") (pin "2") (pinfunction "PA01_2") (pintype "bidirectional"))
    )
    (net (code "71") (name "SERVO2") (class "Default")
      (node (ref "J12") (pin "4") (pinfunction "4_4") (pintype "passive"))
      (node (ref "U1") (pin "1") (pinfunction "PA00_1") (pintype "bidirectional"))
    )
    (net (code "72") (name "SERVO3") (class "Default")
      (node (ref "J12") (pin "7") (pinfunction "7_7") (pintype "passive"))
      (node (ref "U1") (pin "13") (pinfunction "PA08_13") (pintype "bidirectional"))
    )
    (net (code "73") (name "SERVO4") (class "Default")
      (node (ref "J12") (pin "10") (pinfunction "10_10") (pintype "passive"))
      (node (ref "U1") (pin "14") (pinfunction "PA09_14") (pintype "bidirectional"))
    )
    (net (code "74") (name "SONAR1ECHO") (class "Default")
      (node (ref "U1") (pin "41") (pinfunction "PA28_41") (pintype "bidirectional"))
      (node (ref "U7") (pin "5") (pinfunction "A4_5") (pintype "bidirectional"))
    )
    (net (code "75") (name "SONAR1TRIG") (class "Default")
      (node (ref "J10") (pin "2") (pinfunction "2_2") (pintype "passive"))
      (node (ref "U1") (pin "39") (pinfunction "PA27_39") (pintype "bidirectional"))
    )
    (net (code "76") (name "SONAR2ECHO") (class "Default")
      (node (ref "U1") (pin "47") (pinfunction "PB02_47") (pintype "bidirectional"))
      (node (ref "U7") (pin "4") (pinfunction "A3_4") (pintype "bidirectional"))
    )
    (net (code "77") (name "SONAR2TRIG") (class "Default")
      (node (ref "J9") (pin "2") (pinfunction "2_2") (pintype "passive"))
      (node (ref "U1") (pin "38") (pinfunction "PB23_38") (pintype "bidirectional"))
    )
    (net (code "78") (name "SONAR3ECHO") (class "Default")
      (node (ref "U1") (pin "48") (pinfunction "PB03_48") (pintype "bidirectional"))
      (node (ref "U7") (pin "3") (pinfunction "A2_3") (pintype "bidirectional"))
    )
    (net (code "79") (name "SONAR3TRIG") (class "Default")
      (node (ref "J8") (pin "2") (pinfunction "2_2") (pintype "passive"))
      (node (ref "U1") (pin "37") (pinfunction "PB22_37") (pintype "bidirectional"))
    )
    (net (code "80") (name "SWCLK") (class "Default")
      (node (ref "R11") (pin "2") (pinfunction "2_2") (pintype "passive"))
      (node (ref "TP2") (pin "TP") (pinfunction "TP_TP") (pintype "input"))
      (node (ref "U1") (pin "45") (pinfunction "PA30_45") (pintype "bidirectional"))
    )
    (net (code "81") (name "SWDIO") (class "Default")
      (node (ref "TP3") (pin "TP") (pinfunction "TP_TP") (pintype "input"))
      (node (ref "U1") (pin "46") (pinfunction "PA31_46") (pintype "bidirectional"))
    )
    (net (code "82") (name "TX") (class "Default")
      (node (ref "J17") (pin "P$2") (pinfunction "2_P$2") (pintype "passive"))
      (node (ref "U1") (pin "19") (pinfunction "PB10_19") (pintype "bidirectional"))
    )
    (net (code "83") (name "VSENSE") (class "Default")
      (node (ref "R5") (pin "1") (pinfunction "1_1") (pintype "passive"))
      (node (ref "R6") (pin "1") (pinfunction "1_1") (pintype "passive"))
      (node (ref "U1") (pin "12") (pinfunction "PA07_12") (pintype "bidirectional"))
    )
    (net (code "84") (name "unconnected-(J15-Pad1)") (class "Default")
      (node (ref "J15") (pin "1") (pinfunction "1_1") (pintype "passive"))
    )
    (net (code "85") (name "unconnected-(J15-Pad5)") (class "Default")
      (node (ref "J15") (pin "5") (pinfunction "5_5") (pintype "passive"))
    )
    (net (code "86") (name "unconnected-(J17-4-PadP$4)") (class "Default")
      (node (ref "J17") (pin "P$4") (pinfunction "4_P$4") (pintype "passive"))
    )
    (net (code "87") (name "unconnected-(J17-5-PadP$5)") (class "Default")
      (node (ref "J17") (pin "P$5") (pinfunction "5_P$5") (pintype "passive"))
    )
    (net (code "88") (name "unconnected-(U1-PA03-Pad4)") (class "Default")
      (node (ref "U1") (pin "4") (pinfunction "PA03_4") (pintype "bidirectional"))
    )
    (net (code "89") (name "unconnected-(U1-PA11-Pad16)") (class "Default")
      (node (ref "U1") (pin "16") (pinfunction "PA11_16") (pintype "bidirectional"))
    )
    (net (code "90") (name "unconnected-(U4-AUX_CL-Pad7)") (class "Default")
      (node (ref "U4") (pin "7") (pinfunction "AUX_CL_7") (pintype "input"))
    )
    (net (code "91") (name "unconnected-(U4-AUX_DA-Pad6)") (class "Default")
      (node (ref "U4") (pin "6") (pinfunction "AUX_DA_6") (pintype "bidirectional"))
    )
    (net (code "92") (name "unconnected-(U4-INT-Pad12)") (class "Default")
      (node (ref "U4") (pin "12") (pinfunction "INT_12") (pintype "output"))
    )
    (net (code "93") (name "unconnected-(U4-RESV-Pad19)") (class "Default")
      (node (ref "U4") (pin "19") (pinfunction "RESV_19") (pintype "passive"))
    )
    (net (code "94") (name "unconnected-(U4-RESV-Pad21)") (class "Default")
      (node (ref "U4") (pin "21") (pinfunction "RESV_21") (pintype "passive"))
    )
    (net (code "95") (name "unconnected-(U4-RESV-Pad22)") (class "Default")
      (node (ref "U4") (pin "22") (pinfunction "RESV_22") (pintype "passive"))
    )
    (net (code "96") (name "unconnected-(U7-A1-Pad2)") (class "Default")
      (node (ref "U7") (pin "2") (pinfunction "A1_2") (pintype "bidirectional"))
    )
    (net (code "97") (name "unconnected-(U7-B1-Pad13)") (class "Default")
      (node (ref "U7") (pin "13") (pinfunction "B1_13") (pintype "bidirectional"))
    )
    (net (code "98") (name "unconnected-(U7-NC-Pad9)") (class "Default")
      (node (ref "U7") (pin "9") (pinfunction "NC_9") (pintype "no_connect"))
    )
    (net (code "99") (name "unconnected-(U7-NC_2-Pad6)") (class "Default")
      (node (ref "U7") (pin "6") (pinfunction "NC_2_6") (pintype "no_connect"))
    )
    (net (code "100") (name "unconnected-(USB1-ID-Pad4)") (class "Default")
      (node (ref "USB1") (pin "4") (pinfunction "ID_4") (pintype "bidirectional"))
    )
    (net (code "101") (name "unconnected-(USB1-VCC-Pad1)") (class "Default")
      (node (ref "USB1") (pin "1") (pinfunction "VCC_1") (pintype "bidirectional"))
    )
    (net (code "102") (name "~{RESET}") (class "Default")
      (node (ref "C14") (pin "1") (pinfunction "1_1") (pintype "passive"))
      (node (ref "J14") (pin "1") (pinfunction "1_1") (pintype "passive"))
      (node (ref "J14") (pin "2") (pinfunction "2_2") (pintype "passive"))
      (node (ref "R10") (pin "2") (pinfunction "2_2") (pintype "passive"))
      (node (ref "TP1") (pin "TP") (pinfunction "TP_TP") (pintype "input"))
      (node (ref "U1") (pin "40") (pinfunction "RSTN_40") (pintype "bidirectional"))
    )
  )
)
